# Microcontroller.net
KiCad netlist of a schematic drawn in Altium Designer
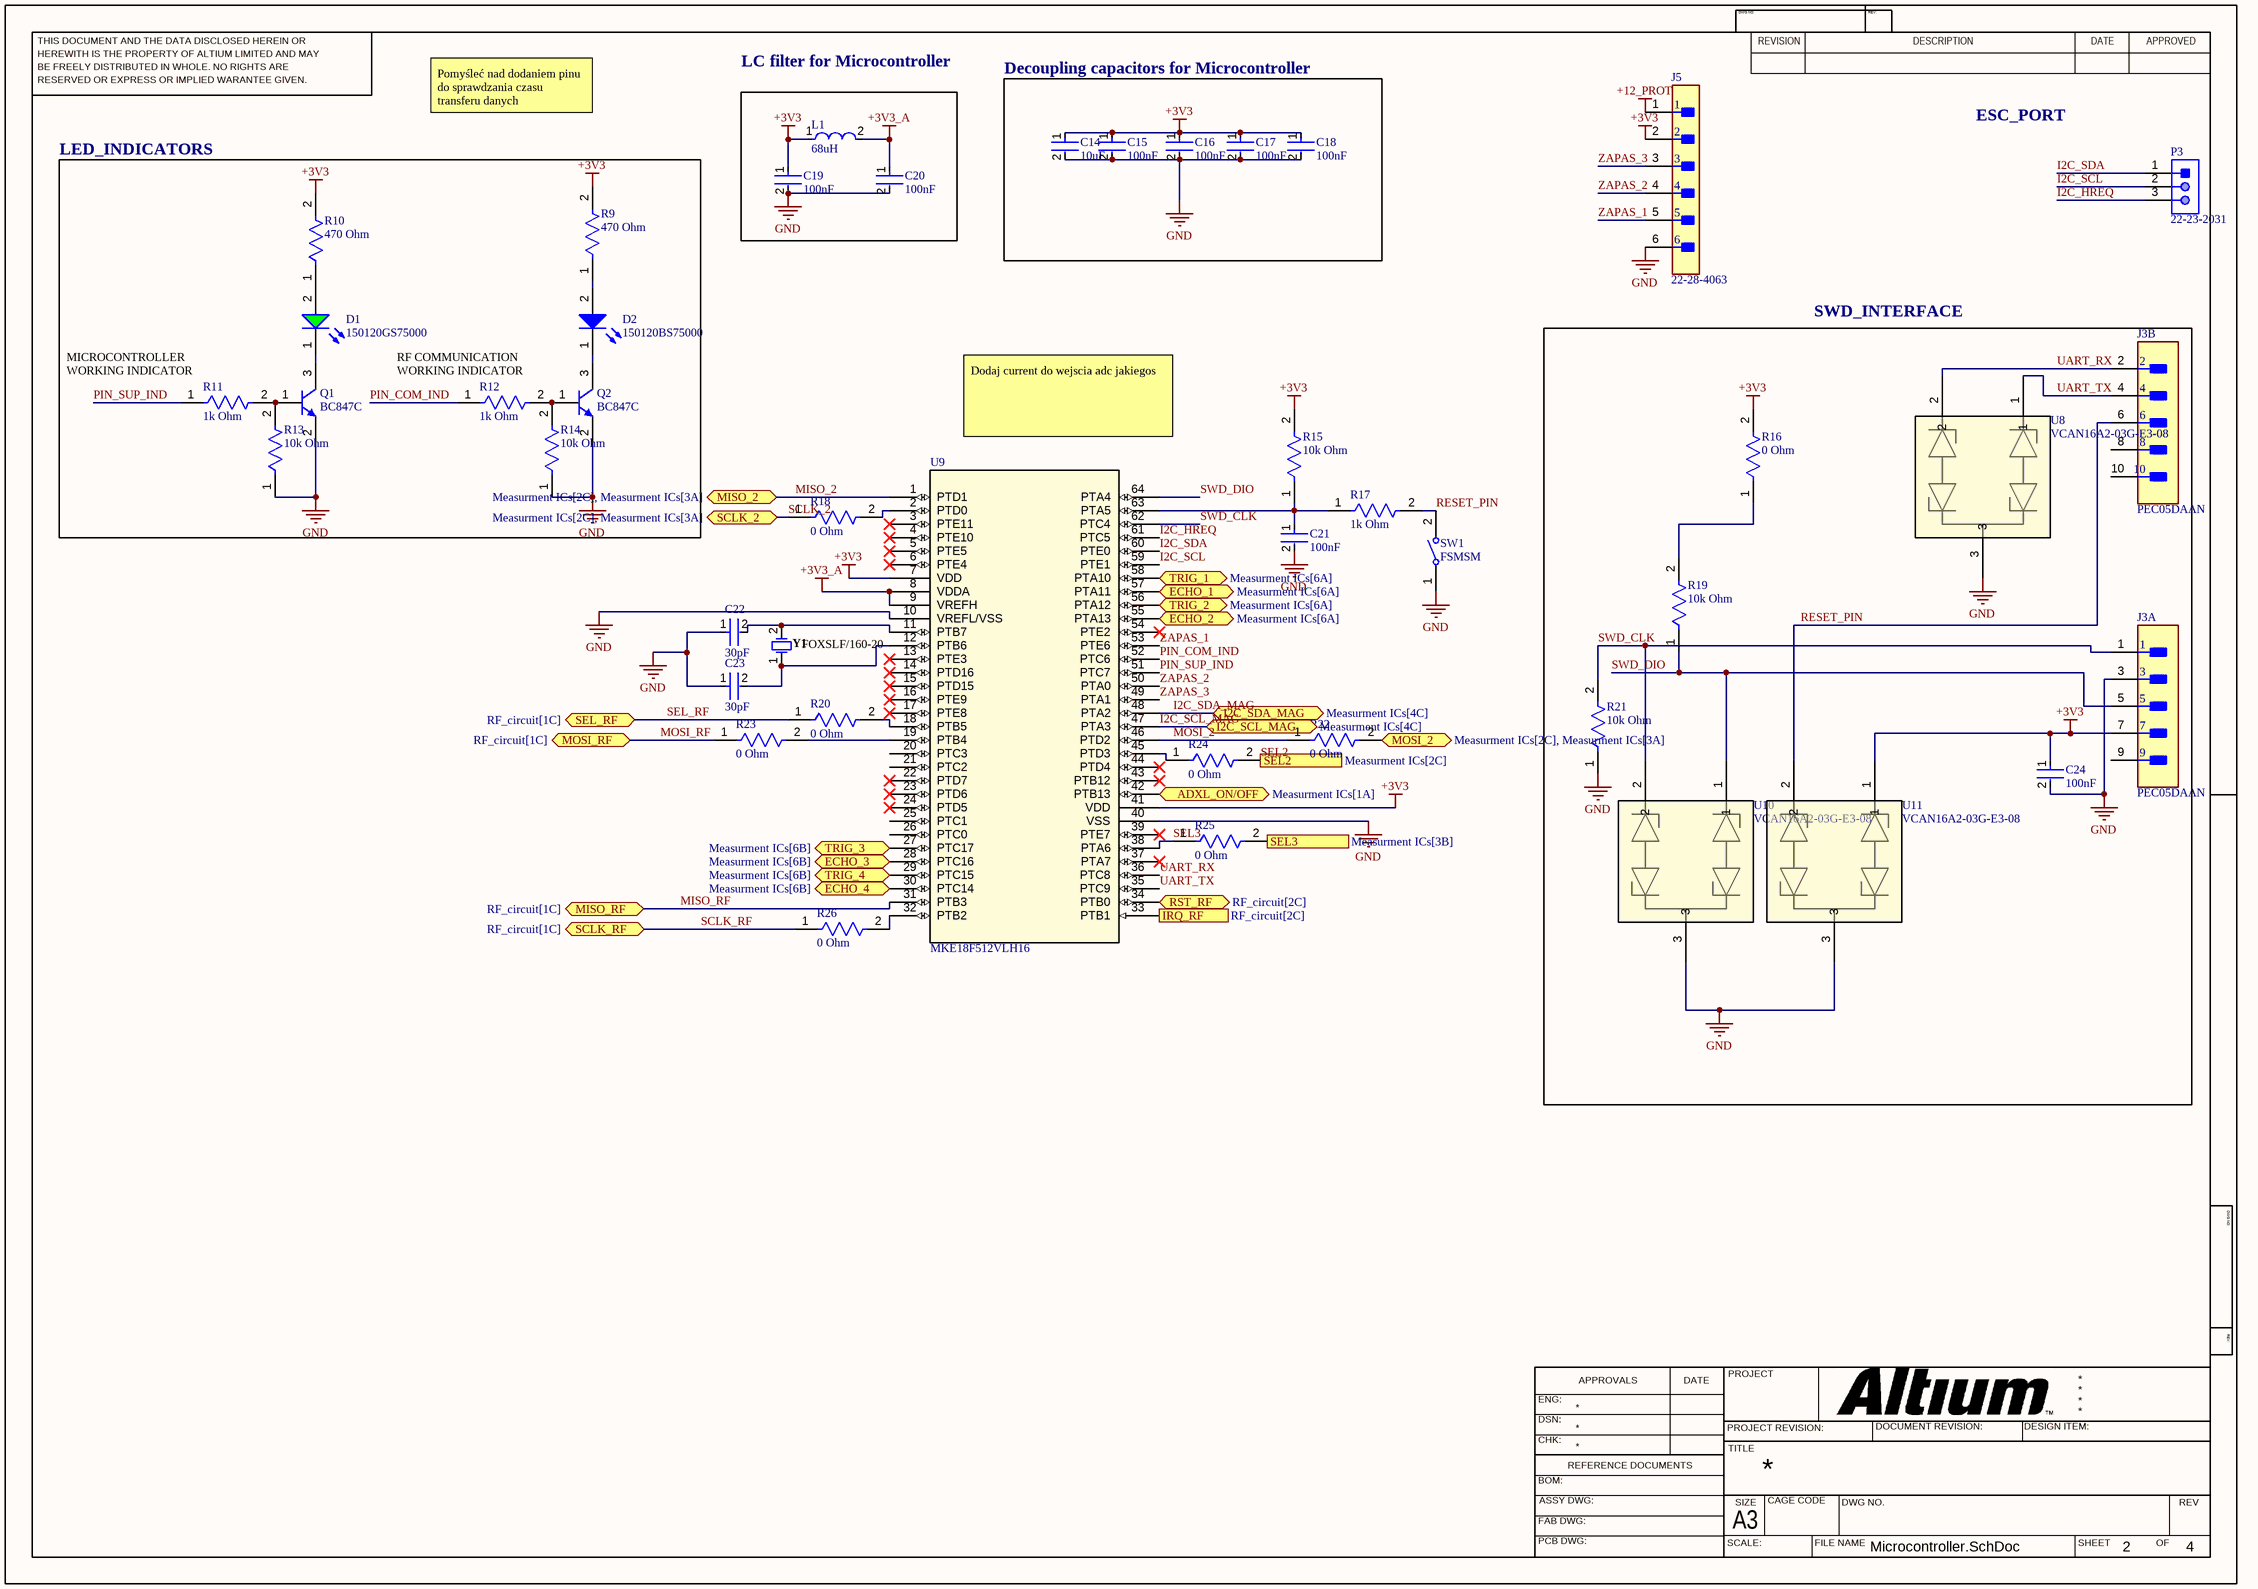
[diagram p0: Microcontroller.SchDoc]

(export (version "E")
  (design (tool "Eeschema 10.0.6"))
  (components
    (comp (ref "C14")
      (value "10uF")
      (footprint "FP-CC0805-0_85-MFG")
      (description "CAP CER 0.1UF 50V X7R 0805")
      (fields (field (name "TOLERANCE") "0.1") (field (name "MANUFACTURER PART NUMBER") "CC0805KRX7R9BB104"))
      (libsource (lib "Altium Content Vault") (part "11868f565c42a9108669ba33697ecf6"))
    )
    (comp (ref "C15")
      (value "100nF")
      (footprint "FP-CC0805-0_85-MFG")
      (description "CAP CER 0.1UF 50V X7R 0805")
      (fields (field (name "TOLERANCE") "0.1") (field (name "MANUFACTURER PART NUMBER") "CC0805KRX7R9BB104"))
      (libsource (lib "Altium Content Vault") (part "11868f565c42a9108669ba33697ecf6"))
    )
    (comp (ref "C16")
      (value "100nF")
      (footprint "FP-CC0805-0_85-MFG")
      (description "CAP CER 0.1UF 50V X7R 0805")
      (fields (field (name "TOLERANCE") "0.1") (field (name "MANUFACTURER PART NUMBER") "CC0805KRX7R9BB104"))
      (libsource (lib "Altium Content Vault") (part "11868f565c42a9108669ba33697ecf6"))
    )
    (comp (ref "C17")
      (value "100nF")
      (footprint "FP-CC0805-0_85-MFG")
      (description "CAP CER 0.1UF 50V X7R 0805")
      (fields (field (name "TOLERANCE") "0.1") (field (name "MANUFACTURER PART NUMBER") "CC0805KRX7R9BB104"))
      (libsource (lib "Altium Content Vault") (part "11868f565c42a9108669ba33697ecf6"))
    )
    (comp (ref "C18")
      (value "100nF")
      (footprint "FP-CC0805-0_85-MFG")
      (description "CAP CER 0.1UF 50V X7R 0805")
      (fields (field (name "TOLERANCE") "0.1") (field (name "MANUFACTURER PART NUMBER") "CC0805KRX7R9BB104"))
      (libsource (lib "Altium Content Vault") (part "11868f565c42a9108669ba33697ecf6"))
    )
    (comp (ref "C19")
      (value "100nF")
      (footprint "FP-CC0805-0_85-MFG")
      (description "CAP CER 0.1UF 50V X7R 0805")
      (fields (field (name "TOLERANCE") "0.1") (field (name "MANUFACTURER PART NUMBER") "CC0805KRX7R9BB104"))
      (libsource (lib "Altium Content Vault") (part "11868f565c42a9108669ba33697ecf6"))
    )
    (comp (ref "C20")
      (value "100nF")
      (footprint "FP-CC0805-0_85-MFG")
      (description "CAP CER 0.1UF 50V X7R 0805")
      (fields (field (name "TOLERANCE") "0.1") (field (name "MANUFACTURER PART NUMBER") "CC0805KRX7R9BB104"))
      (libsource (lib "Altium Content Vault") (part "11868f565c42a9108669ba33697ecf6"))
    )
    (comp (ref "C21")
      (value "100nF")
      (footprint "FP-CC0805-0_85-MFG")
      (description "CAP CER 0.1UF 50V X7R 0805")
      (fields (field (name "TOLERANCE") "0.1") (field (name "MANUFACTURER PART NUMBER") "CC0805KRX7R9BB104"))
      (libsource (lib "Altium Content Vault") (part "11868f565c42a9108669ba33697ecf6"))
    )
    (comp (ref "C22")
      (value "30pF")
      (footprint "FP-CC0805-0_85-MFG")
      (description "CAP CER 0.1UF 50V X7R 0805")
      (fields (field (name "TOLERANCE") "0.1") (field (name "MANUFACTURER PART NUMBER") "CC0805KRX7R9BB104"))
      (libsource (lib "Altium Content Vault") (part "11868f565c42a9108669ba33697ecf6"))
    )
    (comp (ref "C23")
      (value "30pF")
      (footprint "FP-CC0805-0_85-MFG")
      (description "CAP CER 0.1UF 50V X7R 0805")
      (fields (field (name "TOLERANCE") "0.1") (field (name "MANUFACTURER PART NUMBER") "CC0805KRX7R9BB104"))
      (libsource (lib "Altium Content Vault") (part "11868f565c42a9108669ba33697ecf6"))
    )
    (comp (ref "C24")
      (value "100nF")
      (footprint "FP-CC0805-0_85-MFG")
      (description "CAP CER 0.1UF 50V X7R 0805")
      (fields (field (name "TOLERANCE") "0.1") (field (name "MANUFACTURER PART NUMBER") "CC0805KRX7R9BB104"))
      (libsource (lib "Altium Content Vault") (part "11868f565c42a9108669ba33697ecf6"))
    )
    (comp (ref "D1")
      (value "150120GS75000")
      (footprint "WL-SMCW_1206_150120xx75000")
      (description "WL-SMCW SMT Mono-Color Chip LED Waterclear")
      (libsource (lib "Altium Content Vault") (part "LED_Green_2A-1K"))
    )
    (comp (ref "D2")
      (value "150120BS75000")
      (footprint "WL-SMCW_1206_150120xx75000")
      (description "WL-SMCW SMT Mono-Color Chip LED Waterclear")
      (libsource (lib "Altium Content Vault") (part "LED_Blue_2A-1K"))
    )
    (comp (ref "J3")
      (value "PEC05DAAN")
      (footprint "FP-PEC05DAAN-MFG")
      (description "CONN HEADER VERT 10POS 2.54MM")
      (libsource (lib "Altium Content Vault") (part "544f42128f4185dcb88ce1ce9bf1982"))
    )
    (comp (ref "J5")
      (value "22-28-4063")
      (footprint "FP-22-28-4063-MFG")
      (description "CONN HEADER VERT 6POS 2.54MM")
      (libsource (lib "Altium Content Vault") (part "f2cb566baf1c37ab5a3b8e90bbeafd6"))
    )
    (comp (ref "L1")
      (value "68uH")
      (footprint "FP-CB2518-MFG")
      (description "SMD Inductors 68uH ±10% 0.31A 1.95Ω 1007")
      (fields (field (name "TOLERANCE") "10%"))
      (libsource (lib "Altium Content Vault") (part "725321dda6339637d4d059423bc1c3c"))
    )
    (comp (ref "P3")
      (value "22-23-2031")
      (footprint "MOLX-22-23-2031_V")
      (description "Male Header, Pitch 2.54 mm, 1 x 3 Position, Height 8.18 mm, Tail Length 3.56 mm, RoHS, Bulk")
      (fields (field (name "MANUFACTURER") "Molex"))
      (libsource (lib "Altium Content Vault") (part "CN-1P-M-R3"))
    )
    (comp (ref "Q1")
      (value "BC847C")
      (footprint "INF-SOT23_L")
      (description "NPN Silicon AF Transistor, 45 V VCEO, 100 mA IC, SOT23, Reel, Green")
      (fields (field (name "MANUFACTURER") "Infineon"))
      (libsource (lib "Altium Content Vault") (part "INF-BJTNPN-BEC-3"))
    )
    (comp (ref "Q2")
      (value "BC847C")
      (footprint "INF-SOT23_L")
      (description "NPN Silicon AF Transistor, 45 V VCEO, 100 mA IC, SOT23, Reel, Green")
      (fields (field (name "MANUFACTURER") "Infineon"))
      (libsource (lib "Altium Content Vault") (part "INF-BJTNPN-BEC-3"))
    )
    (comp (ref "R9")
      (value "470 Ohm")
      (footprint "FP-RMCF0805-MFG")
      (description "RES 0 OHM JUMPER 1/8W 0805")
      (libsource (lib "Altium Content Vault") (part "1029c3af85768c4190bb7ad29bc67b5"))
    )
    (comp (ref "R10")
      (value "470 Ohm")
      (footprint "FP-RMCF0805-MFG")
      (description "RES 0 OHM JUMPER 1/8W 0805")
      (libsource (lib "Altium Content Vault") (part "1029c3af85768c4190bb7ad29bc67b5"))
    )
    (comp (ref "R11")
      (value "1k Ohm")
      (footprint "FP-RMCF0805-MFG")
      (description "RES 0 OHM JUMPER 1/8W 0805")
      (libsource (lib "Altium Content Vault") (part "1029c3af85768c4190bb7ad29bc67b5"))
    )
    (comp (ref "R12")
      (value "1k Ohm")
      (footprint "FP-RMCF0805-MFG")
      (description "RES 0 OHM JUMPER 1/8W 0805")
      (libsource (lib "Altium Content Vault") (part "1029c3af85768c4190bb7ad29bc67b5"))
    )
    (comp (ref "R13")
      (value "10k Ohm")
      (footprint "FP-RMCF0805-MFG")
      (description "RES 0 OHM JUMPER 1/8W 0805")
      (libsource (lib "Altium Content Vault") (part "1029c3af85768c4190bb7ad29bc67b5"))
    )
    (comp (ref "R14")
      (value "10k Ohm")
      (footprint "FP-RMCF0805-MFG")
      (description "RES 0 OHM JUMPER 1/8W 0805")
      (libsource (lib "Altium Content Vault") (part "1029c3af85768c4190bb7ad29bc67b5"))
    )
    (comp (ref "R15")
      (value "10k Ohm")
      (footprint "FP-RMCF0805-MFG")
      (description "RES 0 OHM JUMPER 1/8W 0805")
      (libsource (lib "Altium Content Vault") (part "1029c3af85768c4190bb7ad29bc67b5"))
    )
    (comp (ref "R16")
      (value "0 Ohm")
      (footprint "FP-RMCF0805-MFG")
      (description "RES 0 OHM JUMPER 1/8W 0805")
      (libsource (lib "Altium Content Vault") (part "1029c3af85768c4190bb7ad29bc67b5"))
    )
    (comp (ref "R17")
      (value "1k Ohm")
      (footprint "FP-RMCF0805-MFG")
      (description "RES 0 OHM JUMPER 1/8W 0805")
      (libsource (lib "Altium Content Vault") (part "1029c3af85768c4190bb7ad29bc67b5"))
    )
    (comp (ref "R18")
      (value "0 Ohm")
      (footprint "FP-RMCF0805-MFG")
      (description "RES 0 OHM JUMPER 1/8W 0805")
      (libsource (lib "Altium Content Vault") (part "1029c3af85768c4190bb7ad29bc67b5"))
    )
    (comp (ref "R19")
      (value "10k Ohm")
      (footprint "FP-RMCF0805-MFG")
      (description "RES 0 OHM JUMPER 1/8W 0805")
      (libsource (lib "Altium Content Vault") (part "1029c3af85768c4190bb7ad29bc67b5"))
    )
    (comp (ref "R20")
      (value "0 Ohm")
      (footprint "FP-RMCF0805-MFG")
      (description "RES 0 OHM JUMPER 1/8W 0805")
      (libsource (lib "Altium Content Vault") (part "1029c3af85768c4190bb7ad29bc67b5"))
    )
    (comp (ref "R21")
      (value "10k Ohm")
      (footprint "FP-RMCF0805-MFG")
      (description "RES 0 OHM JUMPER 1/8W 0805")
      (libsource (lib "Altium Content Vault") (part "1029c3af85768c4190bb7ad29bc67b5"))
    )
    (comp (ref "R22")
      (value "0 Ohm")
      (footprint "FP-RMCF0805-MFG")
      (description "RES 0 OHM JUMPER 1/8W 0805")
      (libsource (lib "Altium Content Vault") (part "1029c3af85768c4190bb7ad29bc67b5"))
    )
    (comp (ref "R23")
      (value "0 Ohm")
      (footprint "FP-RMCF0805-MFG")
      (description "RES 0 OHM JUMPER 1/8W 0805")
      (libsource (lib "Altium Content Vault") (part "1029c3af85768c4190bb7ad29bc67b5"))
    )
    (comp (ref "R24")
      (value "0 Ohm")
      (footprint "FP-RMCF0805-MFG")
      (description "RES 0 OHM JUMPER 1/8W 0805")
      (libsource (lib "Altium Content Vault") (part "1029c3af85768c4190bb7ad29bc67b5"))
    )
    (comp (ref "R25")
      (value "0 Ohm")
      (footprint "FP-RMCF0805-MFG")
      (description "RES 0 OHM JUMPER 1/8W 0805")
      (libsource (lib "Altium Content Vault") (part "1029c3af85768c4190bb7ad29bc67b5"))
    )
    (comp (ref "R26")
      (value "0 Ohm")
      (footprint "FP-RMCF0805-MFG")
      (description "RES 0 OHM JUMPER 1/8W 0805")
      (libsource (lib "Altium Content Vault") (part "1029c3af85768c4190bb7ad29bc67b5"))
    )
    (comp (ref "SW1")
      (value "FSMSM")
      (footprint "TECO-FSMSM-2_V")
      (description "FSMSM Push Button Switch, 50 mA, -35 to 85 degC, 2-Pin SMD, RoHS, Bulk")
      (fields (field (name "MANUFACTURER") "TE Connectivity"))
      (libsource (lib "Altium Content Vault") (part "SW-SPST-2_C"))
    )
    (comp (ref "U8")
      (value "VCAN16A2-03G-E3-08")
      (footprint "SOT_3G-E3-08_VIS")
      (description "No Description Available")
      (libsource (lib "VCAN16A2-03G-E3-08") (part "VCAN16A2-03G-E3-08"))
    )
    (comp (ref "U9")
      (value "MKE18F512VLH16")
      (footprint "LQFP64-10x10_NXP")
      (description "No Description Available")
      (libsource (lib "MKE18F512VLH16") (part "MKE18F512VLH16"))
    )
    (comp (ref "U10")
      (value "VCAN16A2-03G-E3-08")
      (footprint "SOT_3G-E3-08_VIS")
      (description "No Description Available")
      (libsource (lib "VCAN16A2-03G-E3-08") (part "VCAN16A2-03G-E3-08"))
    )
    (comp (ref "U11")
      (value "VCAN16A2-03G-E3-08")
      (footprint "SOT_3G-E3-08_VIS")
      (description "No Description Available")
      (libsource (lib "VCAN16A2-03G-E3-08") (part "VCAN16A2-03G-E3-08"))
    )
    (comp (ref "Y1")
      (value "FOXSLF/160-20")
      (footprint "FOX-FOXSLF160-20")
      (description "Resistance Weld Thru-Hole Crystal, 16 MHz, -20 to 70 degC, 2-Pin THD, RoHS, Bulk")
      (fields (field (name "TOLERANCE") "1%"))
      (libsource (lib "Altium Content Vault") (part "XTAL-1-2-2"))
    )
  )
  (nets
    (net (code "1") (name "+3V3") (class "Default")
      (node (ref "C14") (pin "1") (pinfunction "1_1") (pintype "passive"))
      (node (ref "C15") (pin "1") (pinfunction "1_1") (pintype "passive"))
      (node (ref "C16") (pin "1") (pinfunction "1_1") (pintype "passive"))
      (node (ref "C17") (pin "1") (pinfunction "1_1") (pintype "passive"))
      (node (ref "C18") (pin "1") (pinfunction "1_1") (pintype "passive"))
      (node (ref "C19") (pin "1") (pinfunction "1_1") (pintype "passive"))
      (node (ref "C24") (pin "1") (pinfunction "1_1") (pintype "passive"))
      (node (ref "J3") (pin "7") (pinfunction "7_7") (pintype "passive"))
      (node (ref "J5") (pin "2") (pinfunction "2_2") (pintype "passive"))
      (node (ref "L1") (pin "1") (pinfunction "1_1") (pintype "passive"))
      (node (ref "R10") (pin "2") (pinfunction "2_2") (pintype "passive"))
      (node (ref "R15") (pin "2") (pinfunction "2_2") (pintype "passive"))
      (node (ref "R16") (pin "2") (pinfunction "2_2") (pintype "passive"))
      (node (ref "R9") (pin "2") (pinfunction "2_2") (pintype "passive"))
      (node (ref "U11") (pin "1") (pinfunction "1_1") (pintype "passive"))
      (node (ref "U9") (pin "41") (pinfunction "VDD_41") (pintype "power_in"))
      (node (ref "U9") (pin "7") (pinfunction "VDD_7") (pintype "power_in"))
    )
    (net (code "2") (name "+3V3_A") (class "Default")
      (node (ref "C20") (pin "1") (pinfunction "1_1") (pintype "passive"))
      (node (ref "L1") (pin "2") (pinfunction "2_2") (pintype "passive"))
      (node (ref "U9") (pin "8") (pinfunction "VDDA_8") (pintype "power_in"))
      (node (ref "U9") (pin "9") (pinfunction "VREFH_9") (pintype "power_in"))
    )
    (net (code "3") (name "+12_PROT") (class "Default")
      (node (ref "J5") (pin "1") (pinfunction "1_1") (pintype "passive"))
    )
    (net (code "4") (name "/ADXL_ON{slash}OFF") (class "Default")
      (node (ref "U9") (pin "42") (pinfunction "PTB13_42") (pintype "bidirectional"))
    )
    (net (code "5") (name "/ECHO_1") (class "Default")
      (node (ref "U9") (pin "57") (pinfunction "PTA11_57") (pintype "bidirectional"))
    )
    (net (code "6") (name "/ECHO_2") (class "Default")
      (node (ref "U9") (pin "55") (pinfunction "PTA13_55") (pintype "bidirectional"))
    )
    (net (code "7") (name "/ECHO_3") (class "Default")
      (node (ref "U9") (pin "28") (pinfunction "PTC16_28") (pintype "bidirectional"))
    )
    (net (code "8") (name "/ECHO_4") (class "Default")
      (node (ref "U9") (pin "30") (pinfunction "PTC14_30") (pintype "bidirectional"))
    )
    (net (code "9") (name "/I2C_HREQ") (class "Default")
      (node (ref "P3") (pin "3") (pinfunction "3_3") (pintype "passive"))
      (node (ref "U9") (pin "61") (pinfunction "PTC5_61") (pintype "bidirectional"))
    )
    (net (code "10") (name "/I2C_SCL") (class "Default")
      (node (ref "P3") (pin "2") (pinfunction "2_2") (pintype "passive"))
      (node (ref "U9") (pin "59") (pinfunction "PTE1_59") (pintype "bidirectional"))
    )
    (net (code "11") (name "/I2C_SCL_MAG") (class "Default")
      (node (ref "U9") (pin "47") (pinfunction "PTA3_47") (pintype "bidirectional"))
    )
    (net (code "12") (name "/I2C_SDA") (class "Default")
      (node (ref "P3") (pin "1") (pinfunction "1_1") (pintype "passive"))
      (node (ref "U9") (pin "60") (pinfunction "PTE0_60") (pintype "bidirectional"))
    )
    (net (code "13") (name "/I2C_SDA_MAG") (class "Default")
      (node (ref "U9") (pin "48") (pinfunction "PTA2_48") (pintype "bidirectional"))
    )
    (net (code "14") (name "/IRQ_RF") (class "Default")
      (node (ref "U9") (pin "33") (pinfunction "PTB1_33") (pintype "input"))
    )
    (net (code "15") (name "/MISO_2") (class "Default")
      (node (ref "U9") (pin "1") (pinfunction "PTD1_1") (pintype "bidirectional"))
    )
    (net (code "16") (name "/MISO_RF") (class "Default")
      (node (ref "U9") (pin "31") (pinfunction "PTB3_31") (pintype "bidirectional"))
    )
    (net (code "17") (name "/MOSI_2") (class "Default")
      (node (ref "R22") (pin "1") (pinfunction "1_1") (pintype "passive"))
      (node (ref "U9") (pin "46") (pinfunction "PTD2_46") (pintype "bidirectional"))
    )
    (net (code "18") (name "/MOSI_RF") (class "Default")
      (node (ref "R23") (pin "1") (pinfunction "1_1") (pintype "passive"))
    )
    (net (code "19") (name "/PIN_COM_IND") (class "Default")
      (node (ref "R12") (pin "1") (pinfunction "1_1") (pintype "passive"))
      (node (ref "U9") (pin "52") (pinfunction "PTC6_52") (pintype "bidirectional"))
    )
    (net (code "20") (name "/PIN_SUP_IND") (class "Default")
      (node (ref "R11") (pin "1") (pinfunction "1_1") (pintype "passive"))
      (node (ref "U9") (pin "51") (pinfunction "PTC7_51") (pintype "bidirectional"))
    )
    (net (code "21") (name "/RESET_PIN") (class "Default")
      (node (ref "J3") (pin "6") (pinfunction "6_6") (pintype "passive"))
      (node (ref "R17") (pin "2") (pinfunction "2_2") (pintype "passive"))
      (node (ref "SW1") (pin "2") (pinfunction "2_2") (pintype "passive"))
      (node (ref "U11") (pin "2") (pinfunction "2_2") (pintype "passive"))
    )
    (net (code "22") (name "/RST_RF") (class "Default")
      (node (ref "U9") (pin "34") (pinfunction "PTB0_34") (pintype "bidirectional"))
    )
    (net (code "23") (name "/SCLK_2") (class "Default")
      (node (ref "R18") (pin "1") (pinfunction "1_1") (pintype "passive"))
    )
    (net (code "24") (name "/SCLK_RF") (class "Default")
      (node (ref "R26") (pin "1") (pinfunction "1_1") (pintype "passive"))
    )
    (net (code "25") (name "/SEL2") (class "Default")
      (node (ref "R24") (pin "2") (pinfunction "2_2") (pintype "passive"))
    )
    (net (code "26") (name "/SEL3") (class "Default")
      (node (ref "R25") (pin "1") (pinfunction "1_1") (pintype "passive"))
      (node (ref "U9") (pin "38") (pinfunction "PTA6_38") (pintype "bidirectional"))
    )
    (net (code "27") (name "/SEL_RF") (class "Default")
      (node (ref "R20") (pin "1") (pinfunction "1_1") (pintype "passive"))
    )
    (net (code "28") (name "/SWD_CLK") (class "Default")
      (node (ref "J3") (pin "1") (pinfunction "1_1") (pintype "passive"))
      (node (ref "R21") (pin "2") (pinfunction "2_2") (pintype "passive"))
      (node (ref "U10") (pin "2") (pinfunction "2_2") (pintype "passive"))
      (node (ref "U9") (pin "62") (pinfunction "PTC4_62") (pintype "bidirectional"))
    )
    (net (code "29") (name "/SWD_DIO") (class "Default")
      (node (ref "J3") (pin "5") (pinfunction "5_5") (pintype "passive"))
      (node (ref "R19") (pin "1") (pinfunction "1_1") (pintype "passive"))
      (node (ref "U10") (pin "1") (pinfunction "1_1") (pintype "passive"))
      (node (ref "U9") (pin "64") (pinfunction "PTA4_64") (pintype "bidirectional"))
    )
    (net (code "30") (name "/TRIG_1") (class "Default")
      (node (ref "U9") (pin "58") (pinfunction "PTA10_58") (pintype "bidirectional"))
    )
    (net (code "31") (name "/TRIG_2") (class "Default")
      (node (ref "U9") (pin "56") (pinfunction "PTA12_56") (pintype "bidirectional"))
    )
    (net (code "32") (name "/TRIG_3") (class "Default")
      (node (ref "U9") (pin "27") (pinfunction "PTC17_27") (pintype "bidirectional"))
    )
    (net (code "33") (name "/TRIG_4") (class "Default")
      (node (ref "U9") (pin "29") (pinfunction "PTC15_29") (pintype "bidirectional"))
    )
    (net (code "34") (name "/UART_RX") (class "Default")
      (node (ref "J3") (pin "2") (pinfunction "2_2") (pintype "passive"))
      (node (ref "U8") (pin "2") (pinfunction "2_2") (pintype "passive"))
      (node (ref "U9") (pin "36") (pinfunction "PTC8_36") (pintype "bidirectional"))
    )
    (net (code "35") (name "/UART_TX") (class "Default")
      (node (ref "J3") (pin "4") (pinfunction "4_4") (pintype "passive"))
      (node (ref "U8") (pin "1") (pinfunction "1_1") (pintype "passive"))
      (node (ref "U9") (pin "35") (pinfunction "PTC9_35") (pintype "bidirectional"))
    )
    (net (code "36") (name "/ZAPAS_1") (class "Default")
      (node (ref "J5") (pin "5") (pinfunction "5_5") (pintype "passive"))
      (node (ref "U9") (pin "53") (pinfunction "PTE6_53") (pintype "bidirectional"))
    )
    (net (code "37") (name "/ZAPAS_2") (class "Default")
      (node (ref "J5") (pin "4") (pinfunction "4_4") (pintype "passive"))
      (node (ref "U9") (pin "50") (pinfunction "PTA0_50") (pintype "bidirectional"))
    )
    (net (code "38") (name "/ZAPAS_3") (class "Default")
      (node (ref "J5") (pin "3") (pinfunction "3_3") (pintype "passive"))
      (node (ref "U9") (pin "49") (pinfunction "PTA1_49") (pintype "bidirectional"))
    )
    (net (code "39") (name "GND") (class "Default")
      (node (ref "C14") (pin "2") (pinfunction "2_2") (pintype "passive"))
      (node (ref "C15") (pin "2") (pinfunction "2_2") (pintype "passive"))
      (node (ref "C16") (pin "2") (pinfunction "2_2") (pintype "passive"))
      (node (ref "C17") (pin "2") (pinfunction "2_2") (pintype "passive"))
      (node (ref "C18") (pin "2") (pinfunction "2_2") (pintype "passive"))
      (node (ref "C19") (pin "2") (pinfunction "2_2") (pintype "passive"))
      (node (ref "C20") (pin "2") (pinfunction "2_2") (pintype "passive"))
      (node (ref "C21") (pin "2") (pinfunction "2_2") (pintype "passive"))
      (node (ref "C22") (pin "1") (pinfunction "1_1") (pintype "passive"))
      (node (ref "C23") (pin "1") (pinfunction "1_1") (pintype "passive"))
      (node (ref "C24") (pin "2") (pinfunction "2_2") (pintype "passive"))
      (node (ref "J3") (pin "3") (pinfunction "3_3") (pintype "passive"))
      (node (ref "J5") (pin "6") (pinfunction "6_6") (pintype "passive"))
      (node (ref "Q1") (pin "2") (pinfunction "E_2") (pintype "passive"))
      (node (ref "Q2") (pin "2") (pinfunction "E_2") (pintype "passive"))
      (node (ref "R13") (pin "1") (pinfunction "1_1") (pintype "passive"))
      (node (ref "R14") (pin "1") (pinfunction "1_1") (pintype "passive"))
      (node (ref "R21") (pin "1") (pinfunction "1_1") (pintype "passive"))
      (node (ref "SW1") (pin "1") (pinfunction "1_1") (pintype "passive"))
      (node (ref "U10") (pin "3") (pinfunction "3_3") (pintype "passive"))
      (node (ref "U11") (pin "3") (pinfunction "3_3") (pintype "passive"))
      (node (ref "U8") (pin "3") (pinfunction "3_3") (pintype "passive"))
      (node (ref "U9") (pin "10") (pinfunction "VREFL/VSS_10") (pintype "power_in"))
      (node (ref "U9") (pin "40") (pinfunction "VSS_40") (pintype "power_in"))
    )
    (net (code "40") (name "Net-(D1-A)") (class "Default")
      (node (ref "D1") (pin "2") (pinfunction "A_2") (pintype "passive"))
      (node (ref "R10") (pin "1") (pinfunction "1_1") (pintype "passive"))
    )
    (net (code "41") (name "Net-(D1-K)") (class "Default")
      (node (ref "D1") (pin "1") (pinfunction "K_1") (pintype "passive"))
      (node (ref "Q1") (pin "3") (pinfunction "C_3") (pintype "passive"))
    )
    (net (code "42") (name "Net-(D2-A)") (class "Default")
      (node (ref "D2") (pin "2") (pinfunction "A_2") (pintype "passive"))
      (node (ref "R9") (pin "1") (pinfunction "1_1") (pintype "passive"))
    )
    (net (code "43") (name "Net-(D2-K)") (class "Default")
      (node (ref "D2") (pin "1") (pinfunction "K_1") (pintype "passive"))
      (node (ref "Q2") (pin "3") (pinfunction "C_3") (pintype "passive"))
    )
    (net (code "44") (name "Net-(Q1-B)") (class "Default")
      (node (ref "Q1") (pin "1") (pinfunction "B_1") (pintype "passive"))
      (node (ref "R11") (pin "2") (pinfunction "2_2") (pintype "passive"))
      (node (ref "R13") (pin "2") (pinfunction "2_2") (pintype "passive"))
    )
    (net (code "45") (name "Net-(Q2-B)") (class "Default")
      (node (ref "Q2") (pin "1") (pinfunction "B_1") (pintype "passive"))
      (node (ref "R12") (pin "2") (pinfunction "2_2") (pintype "passive"))
      (node (ref "R14") (pin "2") (pinfunction "2_2") (pintype "passive"))
    )
    (net (code "46") (name "Net-(R16-Pad1)") (class "Default")
      (node (ref "R16") (pin "1") (pinfunction "1_1") (pintype "passive"))
      (node (ref "R19") (pin "2") (pinfunction "2_2") (pintype "passive"))
    )
    (net (code "47") (name "Net-(U9-PTA5)") (class "Default")
      (node (ref "C21") (pin "1") (pinfunction "1_1") (pintype "passive"))
      (node (ref "R15") (pin "1") (pinfunction "1_1") (pintype "passive"))
      (node (ref "R17") (pin "1") (pinfunction "1_1") (pintype "passive"))
      (node (ref "U9") (pin "63") (pinfunction "PTA5_63") (pintype "bidirectional"))
    )
    (net (code "48") (name "Net-(U9-PTB2)") (class "Default")
      (node (ref "R26") (pin "2") (pinfunction "2_2") (pintype "passive"))
      (node (ref "U9") (pin "32") (pinfunction "PTB2_32") (pintype "bidirectional"))
    )
    (net (code "49") (name "Net-(U9-PTB4)") (class "Default")
      (node (ref "R23") (pin "2") (pinfunction "2_2") (pintype "passive"))
      (node (ref "U9") (pin "19") (pinfunction "PTB4_19") (pintype "bidirectional"))
    )
    (net (code "50") (name "Net-(U9-PTB5)") (class "Default")
      (node (ref "R20") (pin "2") (pinfunction "2_2") (pintype "passive"))
      (node (ref "U9") (pin "18") (pinfunction "PTB5_18") (pintype "bidirectional"))
    )
    (net (code "51") (name "Net-(U9-PTB6)") (class "Default")
      (node (ref "C23") (pin "2") (pinfunction "2_2") (pintype "passive"))
      (node (ref "U9") (pin "12") (pinfunction "PTB6_12") (pintype "bidirectional"))
      (node (ref "Y1") (pin "1") (pinfunction "1_1") (pintype "passive"))
    )
    (net (code "52") (name "Net-(U9-PTB7)") (class "Default")
      (node (ref "C22") (pin "2") (pinfunction "2_2") (pintype "passive"))
      (node (ref "U9") (pin "11") (pinfunction "PTB7_11") (pintype "bidirectional"))
      (node (ref "Y1") (pin "2") (pinfunction "2_2") (pintype "passive"))
    )
    (net (code "53") (name "Net-(U9-PTD0)") (class "Default")
      (node (ref "R18") (pin "2") (pinfunction "2_2") (pintype "passive"))
      (node (ref "U9") (pin "2") (pinfunction "PTD0_2") (pintype "bidirectional"))
    )
    (net (code "54") (name "Net-(U9-PTD3)") (class "Default")
      (node (ref "R24") (pin "1") (pinfunction "1_1") (pintype "passive"))
      (node (ref "U9") (pin "45") (pinfunction "PTD3_45") (pintype "bidirectional"))
    )
    (net (code "55") (name "unconnected-(J3-Pad8)") (class "Default")
      (node (ref "J3") (pin "8") (pinfunction "8_8") (pintype "passive"))
    )
    (net (code "56") (name "unconnected-(J3-Pad9)") (class "Default")
      (node (ref "J3") (pin "9") (pinfunction "9_9") (pintype "passive"))
    )
    (net (code "57") (name "unconnected-(J3-Pad10)") (class "Default")
      (node (ref "J3") (pin "10") (pinfunction "10_10") (pintype "passive"))
    )
    (net (code "58") (name "unconnected-(R22-Pad2)") (class "Default")
      (node (ref "R22") (pin "2") (pinfunction "2_2") (pintype "passive"))
    )
    (net (code "59") (name "unconnected-(R25-Pad2)") (class "Default")
      (node (ref "R25") (pin "2") (pinfunction "2_2") (pintype "passive"))
    )
    (net (code "60") (name "unconnected-(U9-PTA7-Pad37)") (class "Default")
      (node (ref "U9") (pin "37") (pinfunction "PTA7_37") (pintype "bidirectional+no_connect"))
    )
    (net (code "61") (name "unconnected-(U9-PTB12-Pad43)") (class "Default")
      (node (ref "U9") (pin "43") (pinfunction "PTB12_43") (pintype "bidirectional+no_connect"))
    )
    (net (code "62") (name "unconnected-(U9-PTC0-Pad26)") (class "Default")
      (node (ref "U9") (pin "26") (pinfunction "PTC0_26") (pintype "bidirectional"))
    )
    (net (code "63") (name "unconnected-(U9-PTC1-Pad25)") (class "Default")
      (node (ref "U9") (pin "25") (pinfunction "PTC1_25") (pintype "bidirectional"))
    )
    (net (code "64") (name "unconnected-(U9-PTC2-Pad21)") (class "Default")
      (node (ref "U9") (pin "21") (pinfunction "PTC2_21") (pintype "bidirectional"))
    )
    (net (code "65") (name "unconnected-(U9-PTC3-Pad20)") (class "Default")
      (node (ref "U9") (pin "20") (pinfunction "PTC3_20") (pintype "bidirectional"))
    )
    (net (code "66") (name "unconnected-(U9-PTD4-Pad44)") (class "Default")
      (node (ref "U9") (pin "44") (pinfunction "PTD4_44") (pintype "bidirectional+no_connect"))
    )
    (net (code "67") (name "unconnected-(U9-PTD5-Pad24)") (class "Default")
      (node (ref "U9") (pin "24") (pinfunction "PTD5_24") (pintype "bidirectional+no_connect"))
    )
    (net (code "68") (name "unconnected-(U9-PTD6-Pad23)") (class "Default")
      (node (ref "U9") (pin "23") (pinfunction "PTD6_23") (pintype "bidirectional+no_connect"))
    )
    (net (code "69") (name "unconnected-(U9-PTD7-Pad22)") (class "Default")
      (node (ref "U9") (pin "22") (pinfunction "PTD7_22") (pintype "bidirectional+no_connect"))
    )
    (net (code "70") (name "unconnected-(U9-PTD15-Pad15)") (class "Default")
      (node (ref "U9") (pin "15") (pinfunction "PTD15_15") (pintype "bidirectional+no_connect"))
    )
    (net (code "71") (name "unconnected-(U9-PTD16-Pad14)") (class "Default")
      (node (ref "U9") (pin "14") (pinfunction "PTD16_14") (pintype "bidirectional+no_connect"))
    )
    (net (code "72") (name "unconnected-(U9-PTE2-Pad54)") (class "Default")
      (node (ref "U9") (pin "54") (pinfunction "PTE2_54") (pintype "bidirectional+no_connect"))
    )
    (net (code "73") (name "unconnected-(U9-PTE3-Pad13)") (class "Default")
      (node (ref "U9") (pin "13") (pinfunction "PTE3_13") (pintype "bidirectional+no_connect"))
    )
    (net (code "74") (name "unconnected-(U9-PTE4-Pad6)") (class "Default")
      (node (ref "U9") (pin "6") (pinfunction "PTE4_6") (pintype "bidirectional+no_connect"))
    )
    (net (code "75") (name "unconnected-(U9-PTE5-Pad5)") (class "Default")
      (node (ref "U9") (pin "5") (pinfunction "PTE5_5") (pintype "bidirectional+no_connect"))
    )
    (net (code "76") (name "unconnected-(U9-PTE7-Pad39)") (class "Default")
      (node (ref "U9") (pin "39") (pinfunction "PTE7_39") (pintype "bidirectional+no_connect"))
    )
    (net (code "77") (name "unconnected-(U9-PTE8-Pad17)") (class "Default")
      (node (ref "U9") (pin "17") (pinfunction "PTE8_17") (pintype "bidirectional+no_connect"))
    )
    (net (code "78") (name "unconnected-(U9-PTE9-Pad16)") (class "Default")
      (node (ref "U9") (pin "16") (pinfunction "PTE9_16") (pintype "bidirectional+no_connect"))
    )
    (net (code "79") (name "unconnected-(U9-PTE10-Pad4)") (class "Default")
      (node (ref "U9") (pin "4") (pinfunction "PTE10_4") (pintype "bidirectional+no_connect"))
    )
    (net (code "80") (name "unconnected-(U9-PTE11-Pad3)") (class "Default")
      (node (ref "U9") (pin "3") (pinfunction "PTE11_3") (pintype "bidirectional+no_connect"))
    )
  )
)
